# UART.net
KiCad netlist of a schematic drawn in Altium Designer
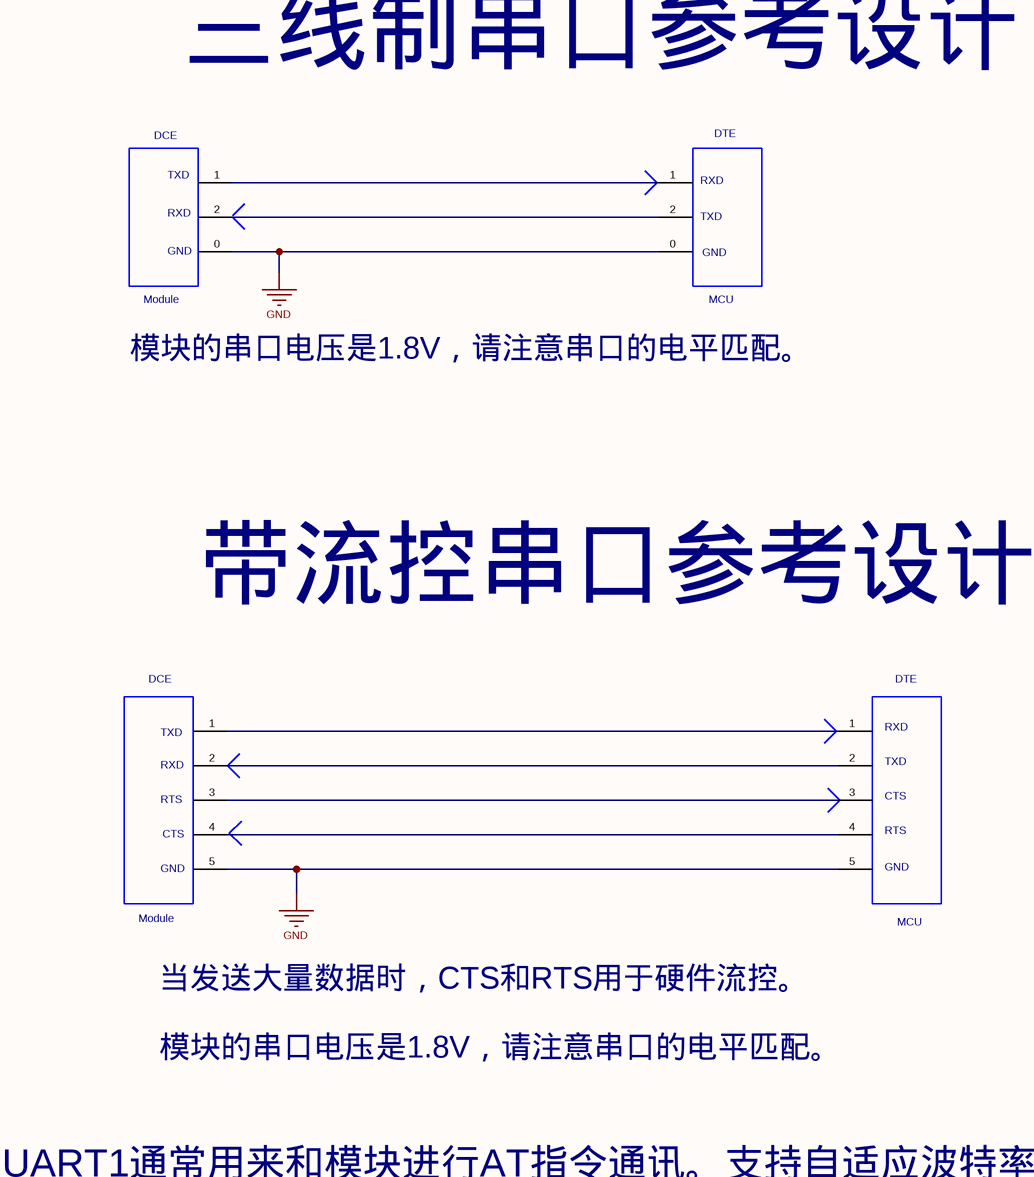
[diagram p0: UART.SchDoc, top left]
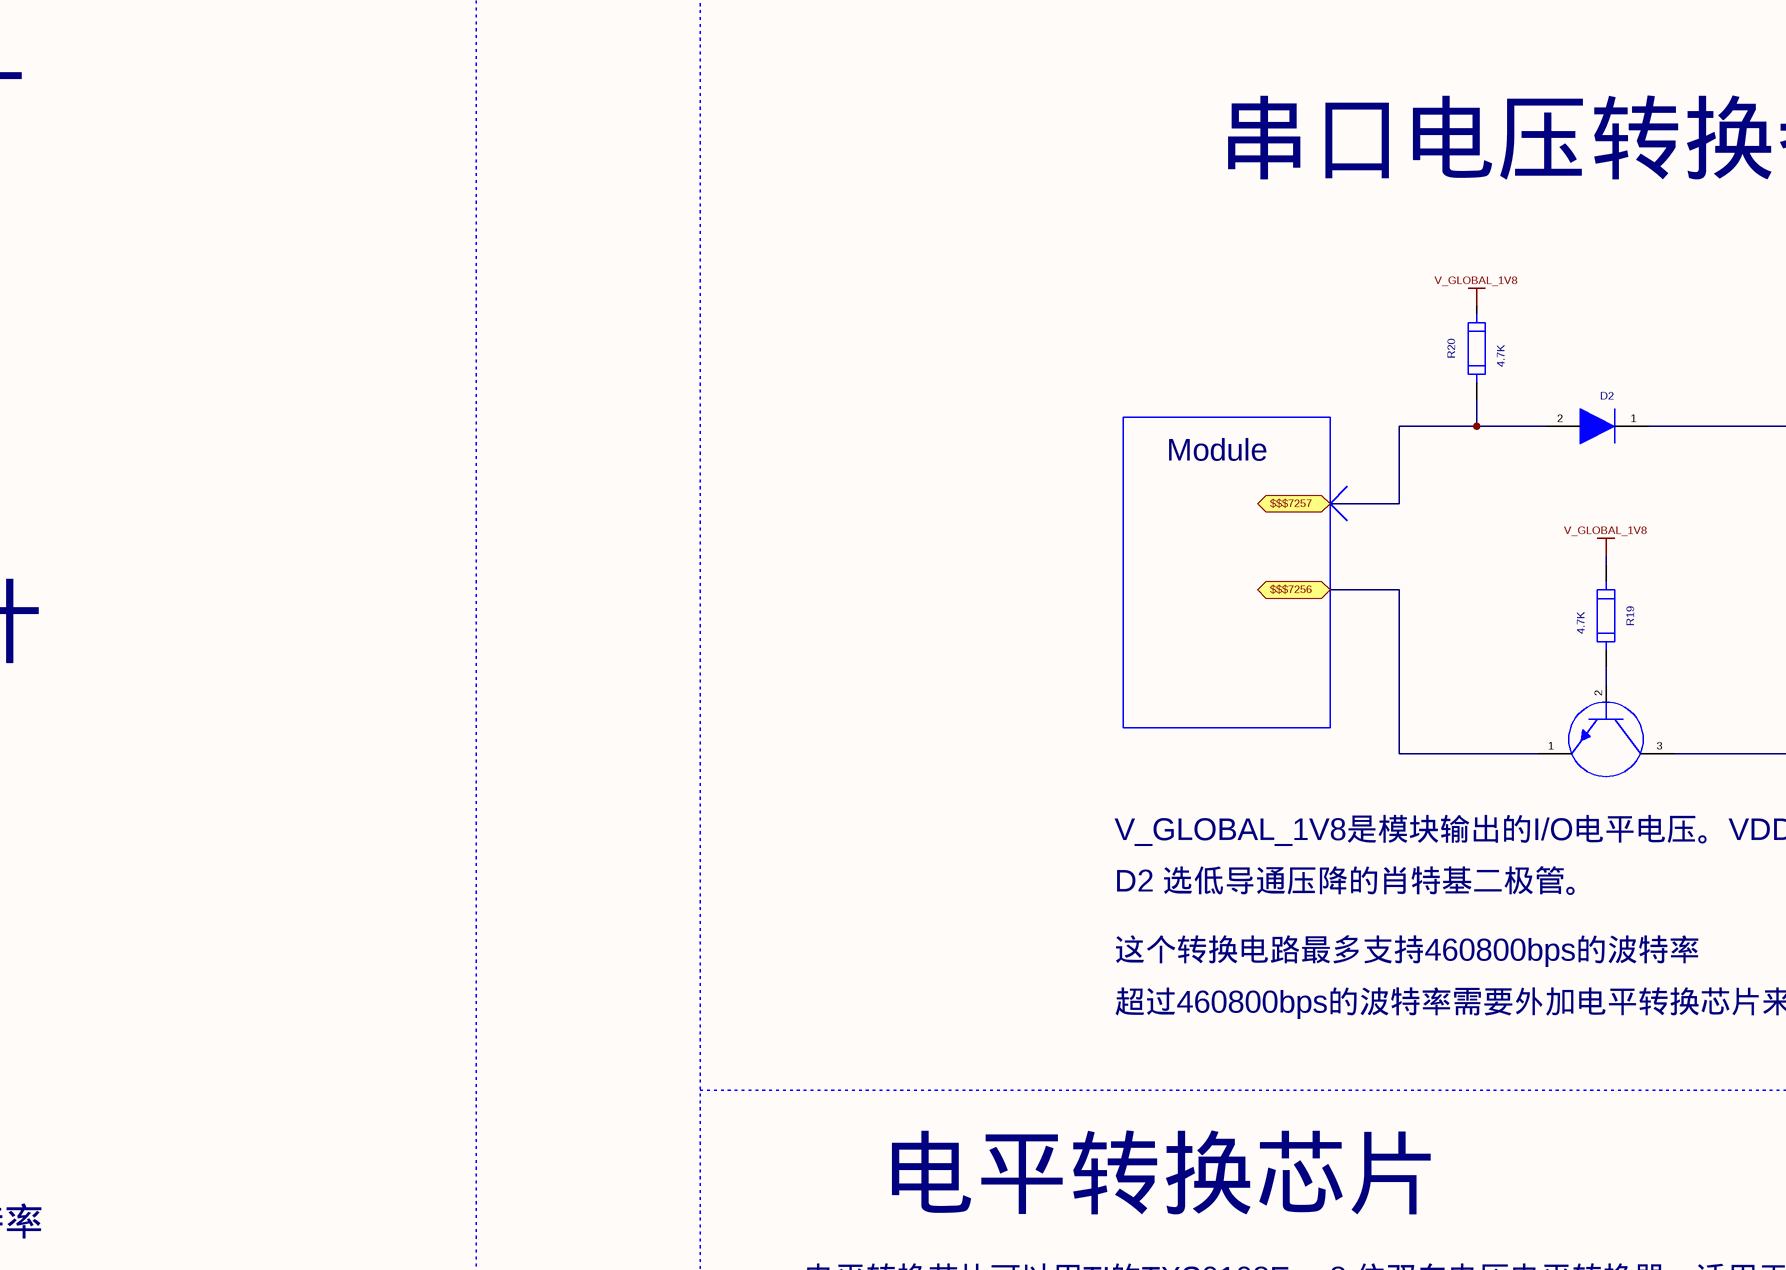
[diagram p1: UART.SchDoc, top middle]
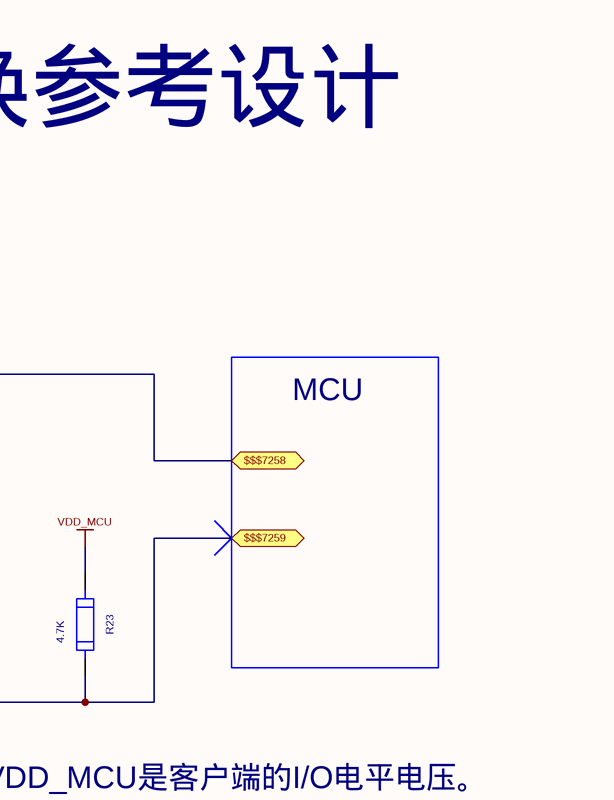
[diagram p2: UART.SchDoc, top right]
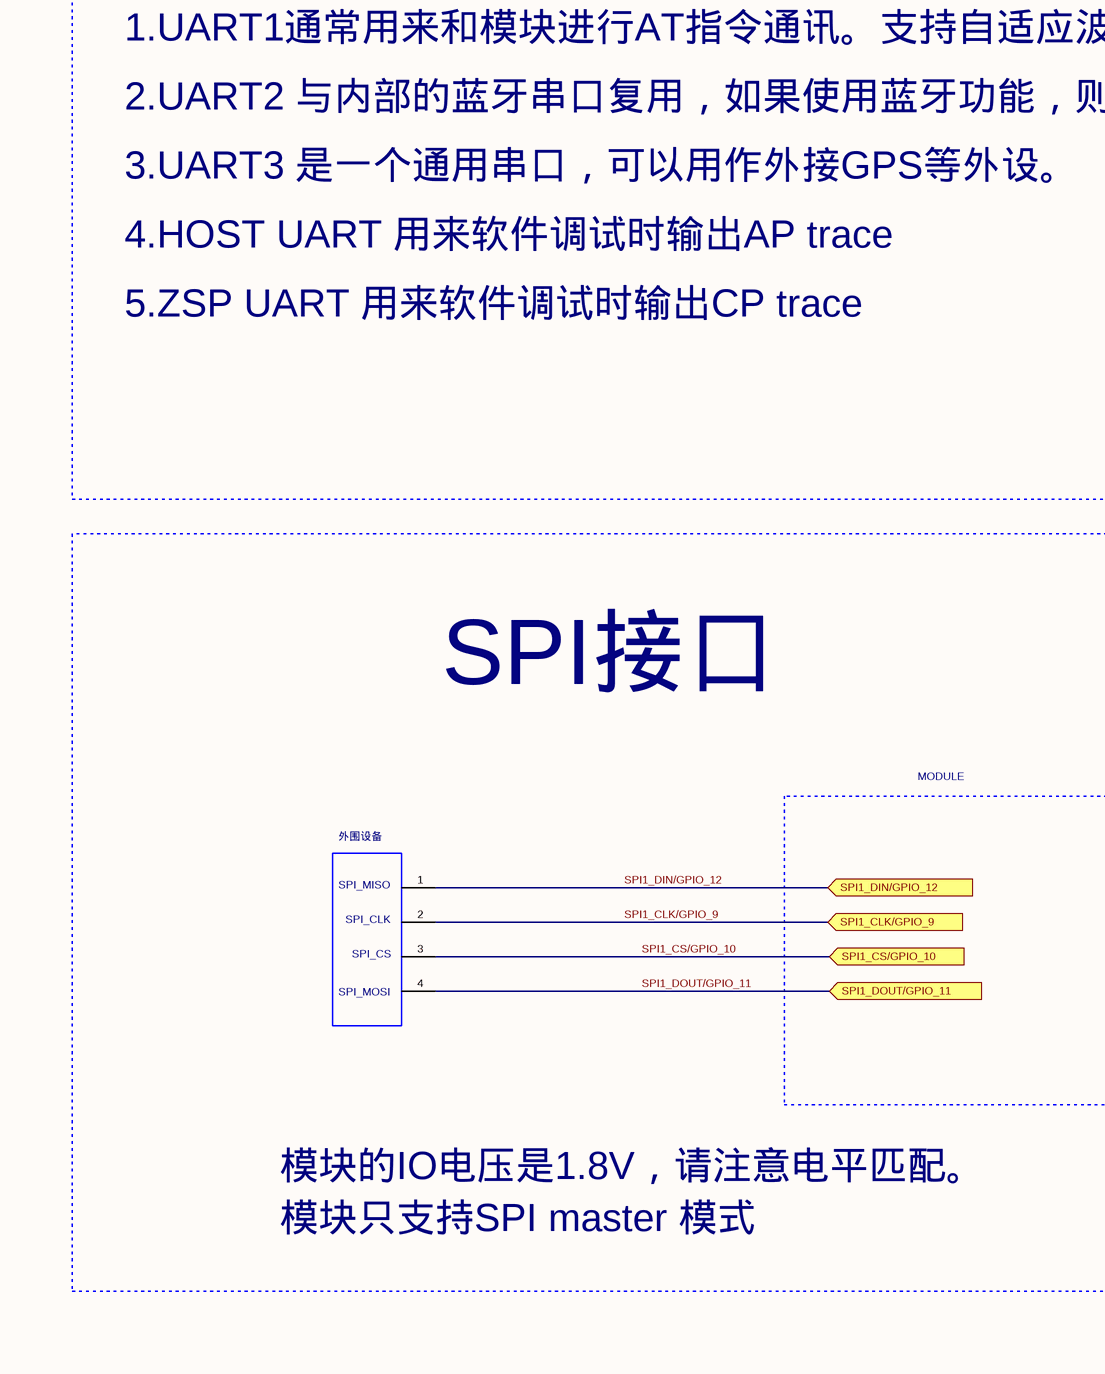
[diagram p3: UART.SchDoc, bottom left]
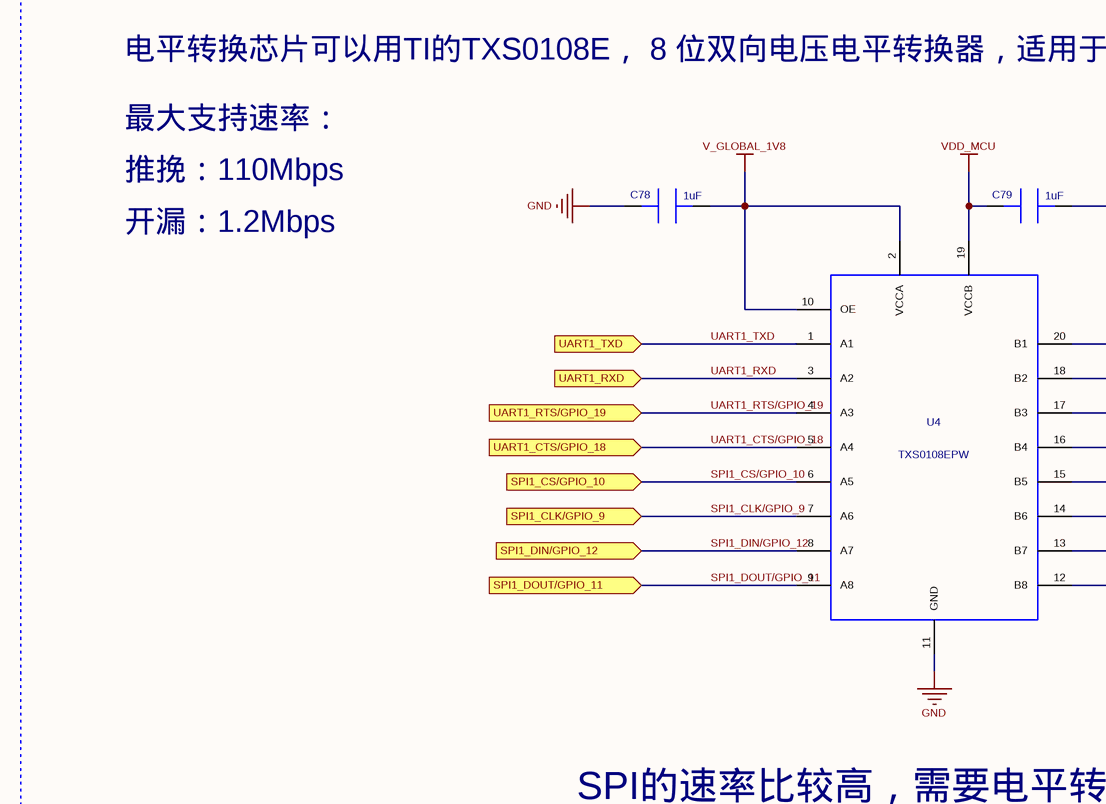
[diagram p4: UART.SchDoc, bottom middle]
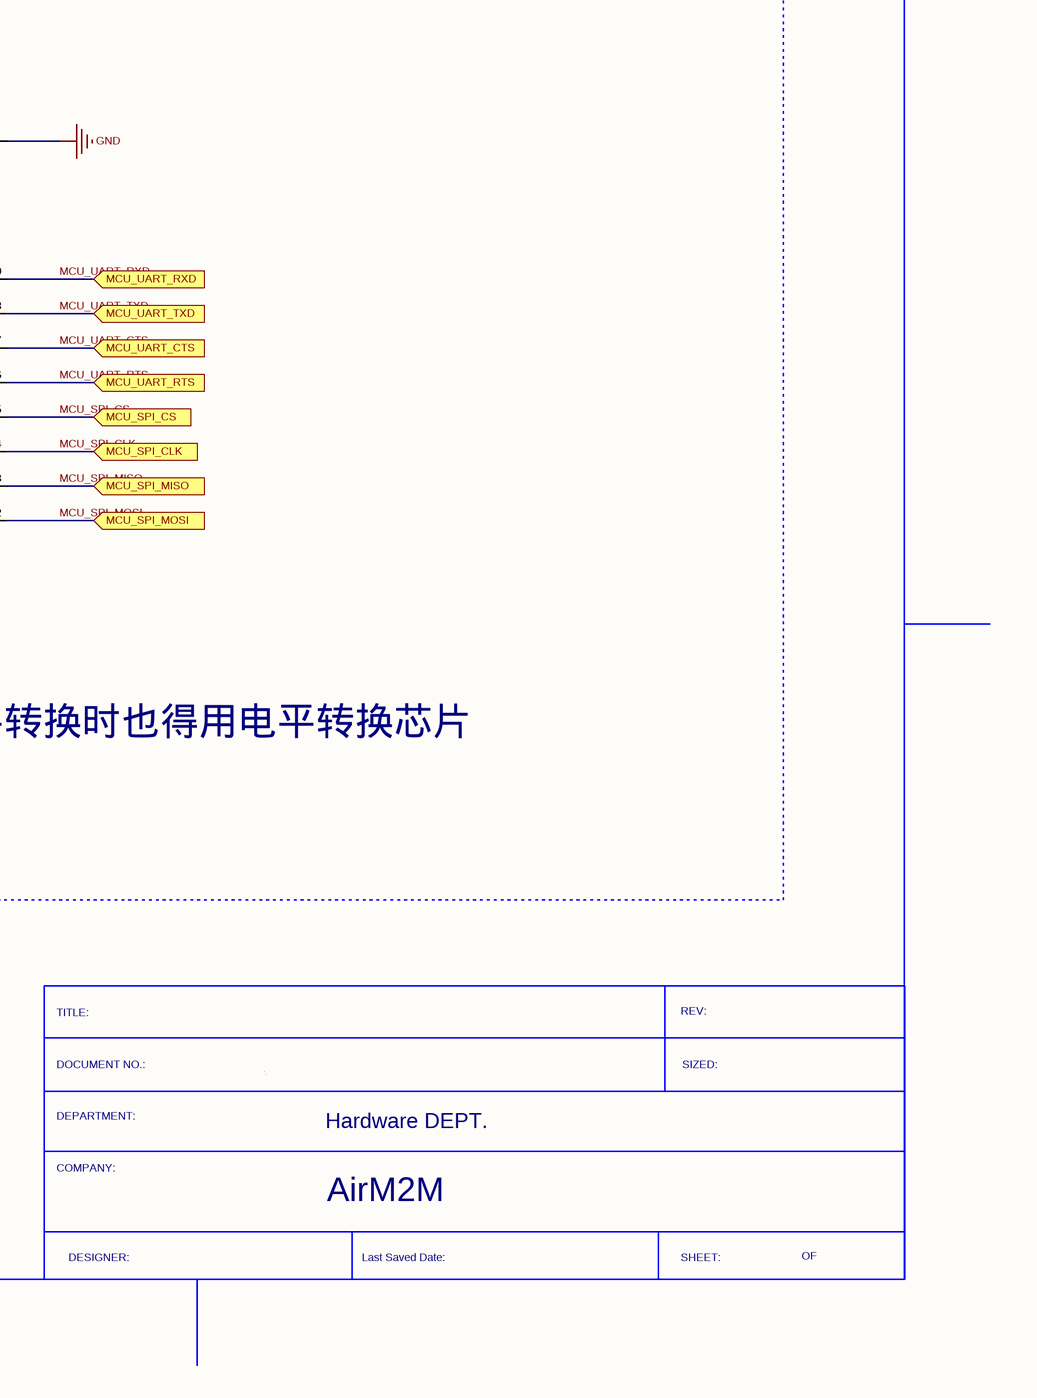
[diagram p5: UART.SchDoc, bottom right]

(export (version "E")
  (design (tool "Eeschema 10.0.6"))
  (components
    (comp (ref "C78")
      (value "1uF")
      (footprint "SC0402")
      (description "CAP CER X5R;1uF;+/-10%;6.3V;0402;0.5mm;ROHS")
      (fields (field (name "TOLERANCE") "+/-10%") (field (name "Comment") "CAP-1UF-0402-X5R"))
      (libsource (lib "*") (part "CAP-1UF-0402-X5R"))
    )
    (comp (ref "C79")
      (value "1uF")
      (footprint "SC0402")
      (description "CAP CER X5R;1uF;+/-10%;6.3V;0402;0.5mm;ROHS")
      (fields (field (name "TOLERANCE") "+/-10%") (field (name "Comment") "CAP-1UF-0402-X5R"))
      (libsource (lib "*") (part "CAP-1UF-0402-X5R"))
    )
    (comp (ref "D2")
      (value "DIODE-SCHOTTKY-RB521S-30")
      (footprint "SOD523(RB521S)")
      (description "Schottky Diode;30V;200mA/0.6V;SOD-523;0.7mm;ROHS")
      (libsource (lib "*") (part "DIODE-SCHOTTKY-RB521S-30"))
    )
    (comp (ref "J27") (value "DIP3X1") (footprint "DIP2X1-2.54") (libsource (lib "*") (part "DIP3X1")))
    (comp (ref "J28") (value "DIP3X1") (footprint "DIP2X1-2.54") (libsource (lib "*") (part "DIP3X1")))
    (comp (ref "J29") (value "DIP5X1") (footprint "DIP2X1-2.54") (libsource (lib "*") (part "DIP5X1")))
    (comp (ref "J30") (value "DIP5X1") (footprint "DIP2X1-2.54") (libsource (lib "*") (part "DIP5X1")))
    (comp (ref "J33") (value "DIP4X1") (footprint "DIP2X1-2.54") (libsource (lib "*") (part "DIP4X1")))
    (comp (ref "Q4")
      (value "TRIODE-NPN-2SC3356")
      (footprint "3PIN-2SC3356")
      (description "Silicon RF Transistor;NPN;12V;0.1A;3-PIN;1.4mm;ROHS")
      (libsource (lib "*") (part "TRIODE-NPN-2SC3356"))
    )
    (comp (ref "R19")
      (value "4.7K")
      (footprint "SR0402")
      (description "RES FILM;4.7K;+/-5%;1/16W;0402;0.4mm;ROHS")
      (fields (field (name "TOLERANCE") "+/-5%") (field (name "Comment") "RES-4.7K-0402"))
      (libsource (lib "*") (part "RES-4.7K-0402"))
    )
    (comp (ref "R20")
      (value "4.7K")
      (footprint "SR0402")
      (description "RES FILM;4.7K;+/-5%;1/16W;0402;0.4mm;ROHS")
      (fields (field (name "TOLERANCE") "+/-5%") (field (name "Comment") "RES-4.7K-0402"))
      (libsource (lib "*") (part "RES-4.7K-0402"))
    )
    (comp (ref "R23")
      (value "4.7K")
      (footprint "SR0402")
      (description "RES FILM;4.7K;+/-5%;1/16W;0402;0.4mm;ROHS")
      (fields (field (name "TOLERANCE") "+/-5%") (field (name "Comment") "RES-4.7K-0402"))
      (libsource (lib "*") (part "RES-4.7K-0402"))
    )
    (comp (ref "U4")
      (value "TXS0108EPW")
      (description "TXS0108E 8 位双向电压电平转换器，适用于漏极开路和推挽应用")
      (libsource (lib "*") (part "TXS0108EPW"))
    )
  )
  (nets
    (net (code "1") (name "/$$$7256") (class "Default")
      (node (ref "Q4") (pin "1") (pinfunction "1_1") (pintype "passive"))
    )
    (net (code "2") (name "/$$$7257") (class "Default")
      (node (ref "D2") (pin "2") (pinfunction "2_2") (pintype "passive"))
      (node (ref "R20") (pin "1") (pinfunction "1_1") (pintype "passive"))
    )
    (net (code "3") (name "/$$$7258") (class "Default")
      (node (ref "D2") (pin "1") (pinfunction "1_1") (pintype "passive"))
    )
    (net (code "4") (name "/$$$7259") (class "Default")
      (node (ref "Q4") (pin "3") (pinfunction "3_3") (pintype "passive"))
      (node (ref "R23") (pin "1") (pinfunction "1_1") (pintype "passive"))
    )
    (net (code "5") (name "/MCU_SPI_CLK") (class "Default")
      (node (ref "U4") (pin "14") (pinfunction "B6_14") (pintype "passive"))
    )
    (net (code "6") (name "/MCU_SPI_CS") (class "Default")
      (node (ref "U4") (pin "15") (pinfunction "B5_15") (pintype "passive"))
    )
    (net (code "7") (name "/MCU_SPI_MISO") (class "Default")
      (node (ref "U4") (pin "13") (pinfunction "B7_13") (pintype "passive"))
    )
    (net (code "8") (name "/MCU_SPI_MOSI") (class "Default")
      (node (ref "U4") (pin "12") (pinfunction "B8_12") (pintype "passive"))
    )
    (net (code "9") (name "/MCU_UART_CTS") (class "Default")
      (node (ref "U4") (pin "17") (pinfunction "B3_17") (pintype "passive"))
    )
    (net (code "10") (name "/MCU_UART_RTS") (class "Default")
      (node (ref "U4") (pin "16") (pinfunction "B4_16") (pintype "passive"))
    )
    (net (code "11") (name "/MCU_UART_RXD") (class "Default")
      (node (ref "U4") (pin "20") (pinfunction "B1_20") (pintype "passive"))
    )
    (net (code "12") (name "/MCU_UART_TXD") (class "Default")
      (node (ref "U4") (pin "18") (pinfunction "B2_18") (pintype "passive"))
    )
    (net (code "13") (name "/SPI1_CLK{slash}GPIO_9") (class "Default")
      (node (ref "J33") (pin "2") (pinfunction "2_2") (pintype "passive"))
      (node (ref "U4") (pin "7") (pinfunction "A6_7") (pintype "passive"))
    )
    (net (code "14") (name "/SPI1_CS{slash}GPIO_10") (class "Default")
      (node (ref "J33") (pin "3") (pinfunction "3_3") (pintype "passive"))
      (node (ref "U4") (pin "6") (pinfunction "A5_6") (pintype "passive"))
    )
    (net (code "15") (name "/SPI1_DIN{slash}GPIO_12") (class "Default")
      (node (ref "J33") (pin "1") (pinfunction "1_1") (pintype "passive"))
      (node (ref "U4") (pin "8") (pinfunction "A7_8") (pintype "passive"))
    )
    (net (code "16") (name "/SPI1_DOUT{slash}GPIO_11") (class "Default")
      (node (ref "J33") (pin "4") (pinfunction "4_4") (pintype "passive"))
      (node (ref "U4") (pin "9") (pinfunction "A8_9") (pintype "passive"))
    )
    (net (code "17") (name "/UART1_CTS{slash}GPIO_18") (class "Default")
      (node (ref "U4") (pin "5") (pinfunction "A4_5") (pintype "passive"))
    )
    (net (code "18") (name "/UART1_RTS{slash}GPIO_19") (class "Default")
      (node (ref "U4") (pin "4") (pinfunction "A3_4") (pintype "passive"))
    )
    (net (code "19") (name "/UART1_RXD") (class "Default")
      (node (ref "U4") (pin "3") (pinfunction "A2_3") (pintype "passive"))
    )
    (net (code "20") (name "/UART1_TXD") (class "Default")
      (node (ref "U4") (pin "1") (pinfunction "A1_1") (pintype "passive"))
    )
    (net (code "21") (name "GND") (class "Default")
      (node (ref "C78") (pin "1") (pinfunction "1_1") (pintype "passive"))
      (node (ref "C79") (pin "2") (pinfunction "2_2") (pintype "passive"))
      (node (ref "J27") (pin "0") (pinfunction "0_0") (pintype "passive"))
      (node (ref "J28") (pin "0") (pinfunction "0_0") (pintype "passive"))
      (node (ref "J29") (pin "5") (pinfunction "5_5") (pintype "passive"))
      (node (ref "J30") (pin "5") (pinfunction "5_5") (pintype "passive"))
      (node (ref "U4") (pin "11") (pinfunction "GND_11") (pintype "passive"))
    )
    (net (code "22") (name "Net-(J27-Pad1)") (class "Default")
      (node (ref "J27") (pin "1") (pinfunction "1_1") (pintype "passive"))
      (node (ref "J28") (pin "1") (pinfunction "1_1") (pintype "passive"))
    )
    (net (code "23") (name "Net-(J27-Pad2)") (class "Default")
      (node (ref "J27") (pin "2") (pinfunction "2_2") (pintype "passive"))
      (node (ref "J28") (pin "2") (pinfunction "2_2") (pintype "passive"))
    )
    (net (code "24") (name "Net-(J29-Pad1)") (class "Default")
      (node (ref "J29") (pin "1") (pinfunction "1_1") (pintype "passive"))
      (node (ref "J30") (pin "1") (pinfunction "1_1") (pintype "passive"))
    )
    (net (code "25") (name "Net-(J29-Pad2)") (class "Default")
      (node (ref "J29") (pin "2") (pinfunction "2_2") (pintype "passive"))
      (node (ref "J30") (pin "2") (pinfunction "2_2") (pintype "passive"))
    )
    (net (code "26") (name "Net-(J29-Pad3)") (class "Default")
      (node (ref "J29") (pin "3") (pinfunction "3_3") (pintype "passive"))
      (node (ref "J30") (pin "3") (pinfunction "3_3") (pintype "passive"))
    )
    (net (code "27") (name "Net-(J29-Pad4)") (class "Default")
      (node (ref "J29") (pin "4") (pinfunction "4_4") (pintype "passive"))
      (node (ref "J30") (pin "4") (pinfunction "4_4") (pintype "passive"))
    )
    (net (code "28") (name "Net-(Q4-Pad2)") (class "Default")
      (node (ref "Q4") (pin "2") (pinfunction "2_2") (pintype "passive"))
      (node (ref "R19") (pin "1") (pinfunction "1_1") (pintype "passive"))
    )
    (net (code "29") (name "VDD_MCU") (class "Default")
      (node (ref "C79") (pin "1") (pinfunction "1_1") (pintype "passive"))
      (node (ref "R23") (pin "2") (pinfunction "2_2") (pintype "passive"))
      (node (ref "U4") (pin "19") (pinfunction "VCCB_19") (pintype "passive"))
    )
    (net (code "30") (name "V_GLOBAL_1V8") (class "Default")
      (node (ref "C78") (pin "2") (pinfunction "2_2") (pintype "passive"))
      (node (ref "R19") (pin "2") (pinfunction "2_2") (pintype "passive"))
      (node (ref "R20") (pin "2") (pinfunction "2_2") (pintype "passive"))
      (node (ref "U4") (pin "10") (pinfunction "OE_10") (pintype "passive"))
      (node (ref "U4") (pin "2") (pinfunction "VCCA_2") (pintype "passive"))
    )
  )
)
